# PM12_ATxmega128.net
KiCad netlist of a schematic drawn in Altium Designer
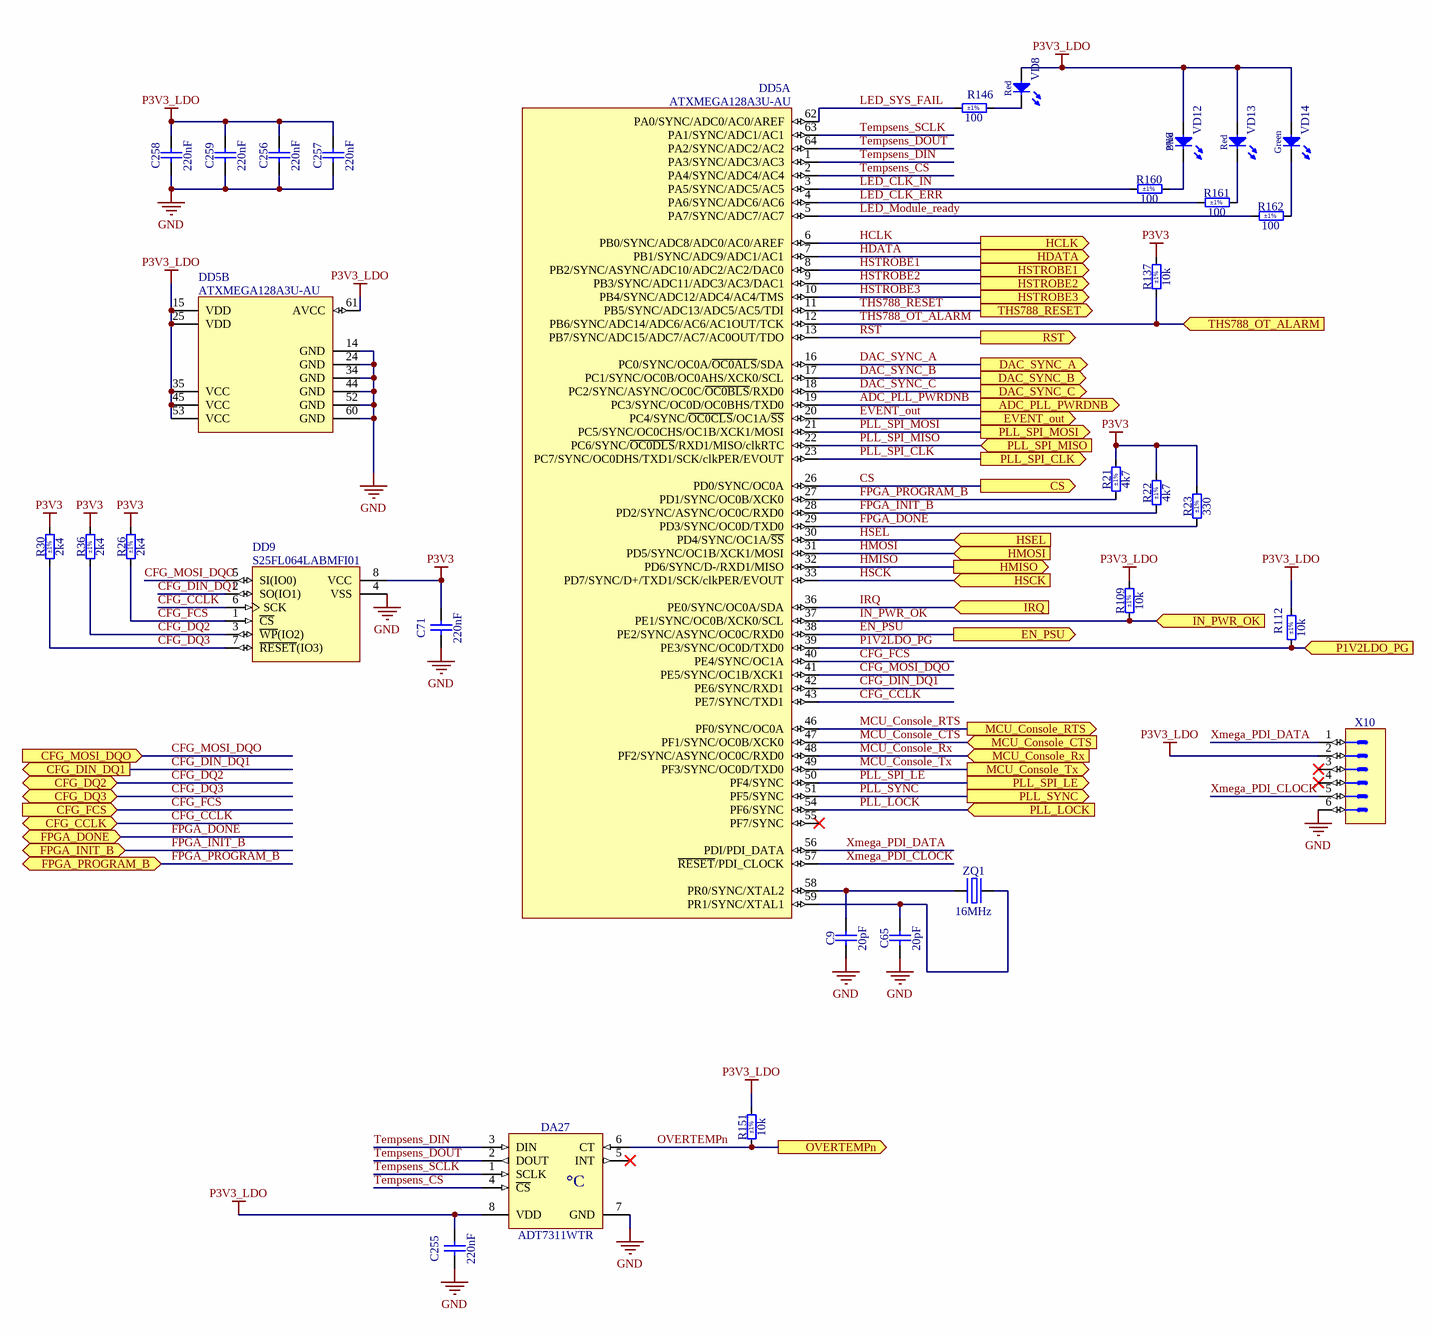
[diagram p0: PM12_ATxmega128.SchDoc]

(export (version "E")
  (design (tool "Eeschema 10.0.6"))
  (components
    (comp (ref "C9")
      (value "20pF")
      (footprint "CAPC2012X135N")
      (description "Non-polarised capacitor")
      (fields
        (field (name "PART NUMBER") "CC0805_20PF_50V_2%_C0G")
        (field (name "VOLTAGE") "50V")
        (field (name "AUTHOR") "CERN DEM HF")
      )
      (libsource (lib "Capacitors") (part "Capacitor - non polarized"))
    )
    (comp (ref "C65")
      (value "20pF")
      (footprint "CAPC2012X135N")
      (description "Non-polarised capacitor")
      (fields
        (field (name "PART NUMBER") "CC0805_20PF_50V_2%_C0G")
        (field (name "VOLTAGE") "50V")
        (field (name "AUTHOR") "CERN DEM HF")
      )
      (libsource (lib "Capacitors") (part "Capacitor - non polarized"))
    )
    (comp (ref "C71")
      (value "220nF")
      (footprint "CAPC2012X135N")
      (description "Non-polarised capacitor")
      (fields
        (field (name "PART NUMBER") "CC0805_220NF_50V_10%_X7R")
        (field (name "VOLTAGE") "50V")
        (field (name "AUTHOR") "CERN DEM JLC")
      )
      (libsource (lib "Capacitors") (part "Capacitor - non polarized"))
    )
    (comp (ref "C255")
      (value "220nF")
      (footprint "CAPC2012X135N")
      (description "Non-polarised capacitor")
      (fields
        (field (name "PART NUMBER") "CC0805_220NF_50V_10%_X7R")
        (field (name "VOLTAGE") "50V")
        (field (name "AUTHOR") "CERN DEM JLC")
      )
      (libsource (lib "Capacitors") (part "Capacitor - non polarized"))
    )
    (comp (ref "C256")
      (value "220nF")
      (footprint "CAPC2012X135N")
      (description "Non-polarised capacitor")
      (fields
        (field (name "PART NUMBER") "CC0805_220NF_50V_10%_X7R")
        (field (name "VOLTAGE") "50V")
        (field (name "AUTHOR") "CERN DEM JLC")
      )
      (libsource (lib "Capacitors") (part "Capacitor - non polarized"))
    )
    (comp (ref "C257")
      (value "220nF")
      (footprint "CAPC2012X135N")
      (description "Non-polarised capacitor")
      (fields
        (field (name "PART NUMBER") "CC0805_220NF_50V_10%_X7R")
        (field (name "VOLTAGE") "50V")
        (field (name "AUTHOR") "CERN DEM JLC")
      )
      (libsource (lib "Capacitors") (part "Capacitor - non polarized"))
    )
    (comp (ref "C258")
      (value "220nF")
      (footprint "CAPC2012X135N")
      (description "Non-polarised capacitor")
      (fields
        (field (name "PART NUMBER") "CC0805_220NF_50V_10%_X7R")
        (field (name "VOLTAGE") "50V")
        (field (name "AUTHOR") "CERN DEM JLC")
      )
      (libsource (lib "Capacitors") (part "Capacitor - non polarized"))
    )
    (comp (ref "C259")
      (value "220nF")
      (footprint "CAPC2012X135N")
      (description "Non-polarised capacitor")
      (fields
        (field (name "PART NUMBER") "CC0805_220NF_50V_10%_X7R")
        (field (name "VOLTAGE") "50V")
        (field (name "AUTHOR") "CERN DEM JLC")
      )
      (libsource (lib "Capacitors") (part "Capacitor - non polarized"))
    )
    (comp (ref "DA27")
      (value "ADT7311WTR")
      (footprint "SOIC127P600X175-8N")
      (description "±0.5°C Accurate, 16-Bit Digital SPI Temperature Sensor")
      (fields (field (name "MANUFACTURER") "ANALOG DEVICES") (field (name "AUTHOR") "CERN DEM HF"))
      (libsource (lib "ICs And Semiconductors") (part "ADT7311WTR"))
    )
    (comp (ref "DD5")
      (value "ATXMEGA128A3U-AU")
      (footprint "QFP80P1600X1600X120-64N")
      (description "8/16-bit XMEGA A3BU 32MHz Microcontroller With 256KBytes of in-System Self-Programmable Flash")
      (fields (field (name "MANUFACTURER") "MICROCHIP TECHNOLOGY") (field (name "AUTHOR") "CERN DEM HF"))
      (libsource (lib "ICs And Semiconductors") (part "ATXMEGA128A3U-AU"))
    )
    (comp (ref "DD9")
      (value "S25FL064LABMFI01")
      (footprint "SOIC127P800X216-8N")
      (description "64 Mb (8 MB), 3V, FL-L SPI Flash Memory")
      (fields (field (name "MANUFACTURER") "INFINEON") (field (name "AUTHOR") "CERN DEM HF"))
      (libsource (lib "ICs And Semiconductors") (part "S25FL064LABMFI01"))
    )
    (comp (ref "R21")
      (value "4k7")
      (footprint "RESC2012X60N")
      (description "Resistor - 1%")
      (fields
        (field (name "TOLERANCE") "±1%")
        (field (name "PART NUMBER") "R0805_4K7_1%_0.125W_100PPM")
        (field (name "POWER") "0.125W")
        (field (name "AUTHOR") "CERN DEM JLC")
      )
      (libsource (lib "Resistors") (part "Resistor - 1%"))
    )
    (comp (ref "R22")
      (value "4k7")
      (footprint "RESC2012X60N")
      (description "Resistor - 1%")
      (fields
        (field (name "TOLERANCE") "±1%")
        (field (name "PART NUMBER") "R0805_4K7_1%_0.125W_100PPM")
        (field (name "POWER") "0.125W")
        (field (name "AUTHOR") "CERN DEM JLC")
      )
      (libsource (lib "Resistors") (part "Resistor - 1%"))
    )
    (comp (ref "R23")
      (value "330")
      (footprint "RESC2012X60N")
      (description "Resistor - 1%")
      (fields
        (field (name "TOLERANCE") "±1%")
        (field (name "PART NUMBER") "R0805_330R_1%_0.125W_100PPM")
        (field (name "POWER") "0.125W")
        (field (name "AUTHOR") "CERN DEM JLC")
      )
      (libsource (lib "Resistors") (part "Resistor - 1%"))
    )
    (comp (ref "R26")
      (value "2k4")
      (footprint "RESC2012X60N")
      (description "Resistor - 1%")
      (fields
        (field (name "TOLERANCE") "±1%")
        (field (name "PART NUMBER") "R0805_2K4_1%_0.125W_100PPM")
        (field (name "POWER") "0.125W")
        (field (name "AUTHOR") "CERN DEM JLC")
      )
      (libsource (lib "Resistors") (part "Resistor - 1%"))
    )
    (comp (ref "R30")
      (value "2k4")
      (footprint "RESC2012X60N")
      (description "Resistor - 1%")
      (fields
        (field (name "TOLERANCE") "±1%")
        (field (name "PART NUMBER") "R0805_2K4_1%_0.125W_100PPM")
        (field (name "POWER") "0.125W")
        (field (name "AUTHOR") "CERN DEM JLC")
      )
      (libsource (lib "Resistors") (part "Resistor - 1%"))
    )
    (comp (ref "R36")
      (value "2k4")
      (footprint "RESC2012X60N")
      (description "Resistor - 1%")
      (fields
        (field (name "TOLERANCE") "±1%")
        (field (name "PART NUMBER") "R0805_2K4_1%_0.125W_100PPM")
        (field (name "POWER") "0.125W")
        (field (name "AUTHOR") "CERN DEM JLC")
      )
      (libsource (lib "Resistors") (part "Resistor - 1%"))
    )
    (comp (ref "R109")
      (value "10k")
      (footprint "RESC2012X60N")
      (description "Resistor - 1%")
      (fields
        (field (name "TOLERANCE") "±1%")
        (field (name "PART NUMBER") "R0805_10K_1%_0.125W_100PPM")
        (field (name "POWER") "0.125W")
        (field (name "AUTHOR") "CERN DEM JLC")
      )
      (libsource (lib "Resistors") (part "Resistor - 1%"))
    )
    (comp (ref "R112")
      (value "10k")
      (footprint "RESC2012X60N")
      (description "Resistor - 1%")
      (fields
        (field (name "TOLERANCE") "±1%")
        (field (name "PART NUMBER") "R0805_10K_1%_0.125W_100PPM")
        (field (name "POWER") "0.125W")
        (field (name "AUTHOR") "CERN DEM JLC")
      )
      (libsource (lib "Resistors") (part "Resistor - 1%"))
    )
    (comp (ref "R137")
      (value "10k")
      (footprint "RESC2012X60N")
      (description "Resistor - 1%")
      (fields
        (field (name "TOLERANCE") "±1%")
        (field (name "PART NUMBER") "R0805_10K_1%_0.125W_100PPM")
        (field (name "POWER") "0.125W")
        (field (name "AUTHOR") "CERN DEM JLC")
      )
      (libsource (lib "Resistors") (part "Resistor - 1%"))
    )
    (comp (ref "R146")
      (value "100")
      (footprint "RESC2012X60N")
      (description "Resistor - 1%")
      (fields
        (field (name "TOLERANCE") "±1%")
        (field (name "PART NUMBER") "R0805_100R_1%_0.125W_100PPM")
        (field (name "POWER") "0.125W")
        (field (name "AUTHOR") "CERN DEM JLC")
      )
      (libsource (lib "Resistors") (part "Resistor - 1%"))
    )
    (comp (ref "R151")
      (value "10k")
      (footprint "RESC2012X60N")
      (description "Resistor - 1%")
      (fields
        (field (name "TOLERANCE") "±1%")
        (field (name "PART NUMBER") "R0805_10K_1%_0.125W_100PPM")
        (field (name "POWER") "0.125W")
        (field (name "AUTHOR") "CERN DEM JLC")
      )
      (libsource (lib "Resistors") (part "Resistor - 1%"))
    )
    (comp (ref "R160")
      (value "100")
      (footprint "RESC2012X60N")
      (description "Resistor - 1%")
      (fields
        (field (name "TOLERANCE") "±1%")
        (field (name "PART NUMBER") "R0805_100R_1%_0.125W_100PPM")
        (field (name "POWER") "0.125W")
        (field (name "AUTHOR") "CERN DEM JLC")
      )
      (libsource (lib "Resistors") (part "Resistor - 1%"))
    )
    (comp (ref "R161")
      (value "100")
      (footprint "RESC2012X60N")
      (description "Resistor - 1%")
      (fields
        (field (name "TOLERANCE") "±1%")
        (field (name "PART NUMBER") "R0805_100R_1%_0.125W_100PPM")
        (field (name "POWER") "0.125W")
        (field (name "AUTHOR") "CERN DEM JLC")
      )
      (libsource (lib "Resistors") (part "Resistor - 1%"))
    )
    (comp (ref "R162")
      (value "100")
      (footprint "RESC2012X60N")
      (description "Resistor - 1%")
      (fields
        (field (name "TOLERANCE") "±1%")
        (field (name "PART NUMBER") "R0805_100R_1%_0.125W_100PPM")
        (field (name "POWER") "0.125W")
        (field (name "AUTHOR") "CERN DEM JLC")
      )
      (libsource (lib "Resistors") (part "Resistor - 1%"))
    )
    (comp (ref "VD8")
      (value "Red")
      (footprint "LED_KINGBRIGHT_KPT-2012SURCK")
      (description "LED Red 1C 2A")
      (fields
        (field (name "PART NUMBER") "LED_KINGBRIGHT_KPT-2012SURCK")
        (field (name "MANUFACTURER") "KINGBRIGHT")
        (field (name "AUTHOR") "CERN DEM BC")
      )
      (libsource (lib "ICs And Semiconductors") (part "LED Red 1C 2A"))
    )
    (comp (ref "VD12")
      (value "Blue")
      (footprint "LED_KINGBRIGHT_KPT-2012VBC-D")
      (description "LED Blue 1C 2A")
      (fields
        (field (name "PART NUMBER") "LED_KINGBRIGHT_KPT-2012VBC-D")
        (field (name "MANUFACTURER") "KINGBRIGHT")
        (field (name "AUTHOR") "CERN DEM BC")
      )
      (libsource (lib "ICs And Semiconductors") (part "LED Blue 1C 2A"))
    )
    (comp (ref "VD13")
      (value "Red")
      (footprint "LED_KINGBRIGHT_KPT-2012SURCK")
      (description "LED Red 1C 2A")
      (fields
        (field (name "PART NUMBER") "LED_KINGBRIGHT_KPT-2012SURCK")
        (field (name "MANUFACTURER") "KINGBRIGHT")
        (field (name "AUTHOR") "CERN DEM BC")
      )
      (libsource (lib "ICs And Semiconductors") (part "LED Red 1C 2A"))
    )
    (comp (ref "VD14")
      (value "Green")
      (footprint "LED_KINGBRIGHT_KP-2012LSGC")
      (description "LED Green 1C 2A")
      (fields
        (field (name "PART NUMBER") "LED_KINGBRIGHT_KP-2012LSGC")
        (field (name "MANUFACTURER") "KINGBRIGHT")
        (field (name "AUTHOR") "CERN DEM BC")
      )
      (libsource (lib "ICs And Semiconductors") (part "LED Green 1C 2A"))
    )
    (comp (ref "X10")
      (value "~")
      (footprint "CONNFLY_DS1013-06SSIB1-B-0")
      (description "Connector 6 Male")
      (fields
        (field (name "PART NUMBER") "CONNFLY_DS1013-06SSIB1-B-0")
        (field (name "MANUFACTURER") "CONNFLY")
        (field (name "AUTHOR") "CERN DEM HF")
      )
      (libsource (lib "Connectors") (part "Connector 6 Male"))
    )
    (comp (ref "ZQ1")
      (value "16MHz")
      (footprint "XTAL_ABRACON_ABL")
      (description "Quartz Crystal")
      (fields
        (field (name "PART NUMBER") "XTAL_16MHZ_ABRACON_ABL-16.000MHZ-B1U")
        (field (name "MANUFACTURER") "ABRACON")
        (field (name "AUTHOR") "CERN DEM HF")
      )
      (libsource (lib "ICs And Semiconductors") (part "Quartz Crystal"))
    )
  )
  (nets
    (net (code "1") (name "/ADC_PLL_PWRDNB") (class "Default")
      (node (ref "DD5") (pin "19") (pinfunction "PC3/SYNC/OC0D/OC0BHS/TXD0_19") (pintype "bidirectional"))
    )
    (net (code "2") (name "/CFG_CCLK") (class "Default")
      (node (ref "DD5") (pin "43") (pinfunction "PE7/SYNC/TXD1_43") (pintype "bidirectional"))
      (node (ref "DD9") (pin "6") (pinfunction "SCK_6") (pintype "input"))
    )
    (net (code "3") (name "/CFG_DIN_DQ1") (class "Default")
      (node (ref "DD5") (pin "42") (pinfunction "PE6/SYNC/RXD1_42") (pintype "bidirectional"))
      (node (ref "DD9") (pin "2") (pinfunction "SO(IO1)_2") (pintype "bidirectional"))
    )
    (net (code "4") (name "/CFG_DQ2") (class "Default")
      (node (ref "DD9") (pin "3") (pinfunction "~{WP}(IO2)_3") (pintype "bidirectional"))
      (node (ref "R36") (pin "1") (pinfunction "1_1") (pintype "passive"))
    )
    (net (code "5") (name "/CFG_DQ3") (class "Default")
      (node (ref "DD9") (pin "7") (pinfunction "~{RESET}(IO3)_7") (pintype "bidirectional"))
      (node (ref "R30") (pin "1") (pinfunction "1_1") (pintype "passive"))
    )
    (net (code "6") (name "/CFG_FCS") (class "Default")
      (node (ref "DD5") (pin "40") (pinfunction "PE4/SYNC/OC1A_40") (pintype "bidirectional"))
      (node (ref "DD9") (pin "1") (pinfunction "~{CS}_1") (pintype "input"))
      (node (ref "R26") (pin "1") (pinfunction "1_1") (pintype "passive"))
    )
    (net (code "7") (name "/CFG_MOSI_DQO") (class "Default")
      (node (ref "DD5") (pin "41") (pinfunction "PE5/SYNC/OC1B/XCK1_41") (pintype "bidirectional"))
      (node (ref "DD9") (pin "5") (pinfunction "SI(IO0)_5") (pintype "bidirectional"))
    )
    (net (code "8") (name "/CS") (class "Default")
      (node (ref "DD5") (pin "26") (pinfunction "PD0/SYNC/OC0A_26") (pintype "bidirectional"))
    )
    (net (code "9") (name "/DAC_SYNC_A") (class "Default")
      (node (ref "DD5") (pin "16") (pinfunction "PC0/SYNC/OC0A/~{OC0ALS}/SDA_16") (pintype "bidirectional"))
    )
    (net (code "10") (name "/DAC_SYNC_B") (class "Default")
      (node (ref "DD5") (pin "17") (pinfunction "PC1/SYNC/OC0B/OC0AHS/XCK0/SCL_17") (pintype "bidirectional"))
    )
    (net (code "11") (name "/DAC_SYNC_C") (class "Default")
      (node (ref "DD5") (pin "18") (pinfunction "PC2/SYNC/ASYNC/OC0C/~{OC0BLS}/RXD0_18") (pintype "bidirectional"))
    )
    (net (code "12") (name "/EN_PSU") (class "Default")
      (node (ref "DD5") (pin "38") (pinfunction "PE2/SYNC/ASYNC/OC0C/RXD0_38") (pintype "bidirectional"))
    )
    (net (code "13") (name "/EVENT_out") (class "Default")
      (node (ref "DD5") (pin "20") (pinfunction "PC4/SYNC/~{OC0CLS}/OC1A/~{SS}_20") (pintype "bidirectional"))
    )
    (net (code "14") (name "/FPGA_DONE") (class "Default")
      (node (ref "DD5") (pin "29") (pinfunction "PD3/SYNC/OC0D/TXD0_29") (pintype "bidirectional"))
      (node (ref "R23") (pin "1") (pinfunction "1_1") (pintype "passive"))
    )
    (net (code "15") (name "/FPGA_INIT_B") (class "Default")
      (node (ref "DD5") (pin "28") (pinfunction "PD2/SYNC/ASYNC/OC0C/RXD0_28") (pintype "bidirectional"))
      (node (ref "R22") (pin "1") (pinfunction "1_1") (pintype "passive"))
    )
    (net (code "16") (name "/FPGA_PROGRAM_B") (class "Default")
      (node (ref "DD5") (pin "27") (pinfunction "PD1/SYNC/OC0B/XCK0_27") (pintype "bidirectional"))
      (node (ref "R21") (pin "1") (pinfunction "1_1") (pintype "passive"))
    )
    (net (code "17") (name "/HCLK") (class "Default")
      (node (ref "DD5") (pin "6") (pinfunction "PB0/SYNC/ADC8/ADC0/AC0/AREF_6") (pintype "bidirectional"))
    )
    (net (code "18") (name "/HDATA") (class "Default")
      (node (ref "DD5") (pin "7") (pinfunction "PB1/SYNC/ADC9/ADC1/AC1_7") (pintype "bidirectional"))
    )
    (net (code "19") (name "/HMISO") (class "Default")
      (node (ref "DD5") (pin "32") (pinfunction "PD6/SYNC/D-/RXD1/MISO_32") (pintype "bidirectional"))
    )
    (net (code "20") (name "/HMOSI") (class "Default")
      (node (ref "DD5") (pin "31") (pinfunction "PD5/SYNC/OC1B/XCK1/MOSI_31") (pintype "bidirectional"))
    )
    (net (code "21") (name "/HSCK") (class "Default")
      (node (ref "DD5") (pin "33") (pinfunction "PD7/SYNC/D+/TXD1/SCK/clkPER/EVOUT_33") (pintype "bidirectional"))
    )
    (net (code "22") (name "/HSEL") (class "Default")
      (node (ref "DD5") (pin "30") (pinfunction "PD4/SYNC/OC1A/~{SS}_30") (pintype "bidirectional"))
    )
    (net (code "23") (name "/HSTROBE1") (class "Default")
      (node (ref "DD5") (pin "8") (pinfunction "PB2/SYNC/ASYNC/ADC10/ADC2/AC2/DAC0_8") (pintype "bidirectional"))
    )
    (net (code "24") (name "/HSTROBE2") (class "Default")
      (node (ref "DD5") (pin "9") (pinfunction "PB3/SYNC/ADC11/ADC3/AC3/DAC1_9") (pintype "bidirectional"))
    )
    (net (code "25") (name "/HSTROBE3") (class "Default")
      (node (ref "DD5") (pin "10") (pinfunction "PB4/SYNC/ADC12/ADC4/AC4/TMS_10") (pintype "bidirectional"))
    )
    (net (code "26") (name "/IN_PWR_OK") (class "Default")
      (node (ref "DD5") (pin "37") (pinfunction "PE1/SYNC/OC0B/XCK0/SCL_37") (pintype "bidirectional"))
      (node (ref "R109") (pin "1") (pinfunction "1_1") (pintype "passive"))
    )
    (net (code "27") (name "/IRQ") (class "Default")
      (node (ref "DD5") (pin "36") (pinfunction "PE0/SYNC/OC0A/SDA_36") (pintype "bidirectional"))
    )
    (net (code "28") (name "/LED_CLK_ERR") (class "Default")
      (node (ref "DD5") (pin "4") (pinfunction "PA6/SYNC/ADC6/AC6_4") (pintype "bidirectional"))
      (node (ref "R161") (pin "1") (pinfunction "1_1") (pintype "passive"))
    )
    (net (code "29") (name "/LED_CLK_IN") (class "Default")
      (node (ref "DD5") (pin "3") (pinfunction "PA5/SYNC/ADC5/AC5_3") (pintype "bidirectional"))
      (node (ref "R160") (pin "1") (pinfunction "1_1") (pintype "passive"))
    )
    (net (code "30") (name "/LED_Module_ready") (class "Default")
      (node (ref "DD5") (pin "5") (pinfunction "PA7/SYNC/ADC7/AC7_5") (pintype "bidirectional"))
      (node (ref "R162") (pin "1") (pinfunction "1_1") (pintype "passive"))
    )
    (net (code "31") (name "/LED_SYS_FAIL") (class "Default")
      (node (ref "DD5") (pin "62") (pinfunction "PA0/SYNC/ADC0/AC0/AREF_62") (pintype "bidirectional"))
      (node (ref "R146") (pin "1") (pinfunction "1_1") (pintype "passive"))
    )
    (net (code "32") (name "/MCU_Console_CTS") (class "Default")
      (node (ref "DD5") (pin "47") (pinfunction "PF1/SYNC/OC0B/XCK0_47") (pintype "bidirectional"))
    )
    (net (code "33") (name "/MCU_Console_RTS") (class "Default")
      (node (ref "DD5") (pin "46") (pinfunction "PF0/SYNC/OC0A_46") (pintype "bidirectional"))
    )
    (net (code "34") (name "/MCU_Console_Rx") (class "Default")
      (node (ref "DD5") (pin "48") (pinfunction "PF2/SYNC/ASYNC/OC0C/RXD0_48") (pintype "bidirectional"))
    )
    (net (code "35") (name "/MCU_Console_Tx") (class "Default")
      (node (ref "DD5") (pin "49") (pinfunction "PF3/SYNC/OC0D/TXD0_49") (pintype "bidirectional"))
    )
    (net (code "36") (name "/OVERTEMPn") (class "Default")
      (node (ref "DA27") (pin "6") (pinfunction "CT_6") (pintype "input"))
      (node (ref "R151") (pin "1") (pinfunction "1_1") (pintype "passive"))
    )
    (net (code "37") (name "/P1V2LDO_PG") (class "Default")
      (node (ref "DD5") (pin "39") (pinfunction "PE3/SYNC/OC0D/TXD0_39") (pintype "bidirectional"))
      (node (ref "R112") (pin "1") (pinfunction "1_1") (pintype "passive"))
    )
    (net (code "38") (name "/PLL_LOCK") (class "Default")
      (node (ref "DD5") (pin "54") (pinfunction "PF6/SYNC_54") (pintype "bidirectional"))
    )
    (net (code "39") (name "/PLL_SPI_CLK") (class "Default")
      (node (ref "DD5") (pin "23") (pinfunction "PC7/SYNC/OC0DHS/TXD1/SCK/clkPER/EVOUT_23") (pintype "bidirectional"))
    )
    (net (code "40") (name "/PLL_SPI_LE") (class "Default")
      (node (ref "DD5") (pin "50") (pinfunction "PF4/SYNC_50") (pintype "bidirectional"))
    )
    (net (code "41") (name "/PLL_SPI_MISO") (class "Default")
      (node (ref "DD5") (pin "22") (pinfunction "PC6/SYNC/~{OC0DLS}/RXD1/MISO/clkRTC_22") (pintype "bidirectional"))
    )
    (net (code "42") (name "/PLL_SPI_MOSI") (class "Default")
      (node (ref "DD5") (pin "21") (pinfunction "PC5/SYNC/OC0CHS/OC1B/XCK1/MOSI_21") (pintype "bidirectional"))
    )
    (net (code "43") (name "/PLL_SYNC") (class "Default")
      (node (ref "DD5") (pin "51") (pinfunction "PF5/SYNC_51") (pintype "bidirectional"))
    )
    (net (code "44") (name "/RST") (class "Default")
      (node (ref "DD5") (pin "13") (pinfunction "PB7/SYNC/ADC15/ADC7/AC7/AC0OUT/TDO_13") (pintype "bidirectional"))
    )
    (net (code "45") (name "/THS788_OT_ALARM") (class "Default")
      (node (ref "DD5") (pin "12") (pinfunction "PB6/SYNC/ADC14/ADC6/AC6/AC1OUT/TCK_12") (pintype "bidirectional"))
      (node (ref "R137") (pin "1") (pinfunction "1_1") (pintype "passive"))
    )
    (net (code "46") (name "/THS788_RESET") (class "Default")
      (node (ref "DD5") (pin "11") (pinfunction "PB5/SYNC/ADC13/ADC5/AC5/TDI_11") (pintype "bidirectional"))
    )
    (net (code "47") (name "/Tempsens_CS") (class "Default")
      (node (ref "DA27") (pin "4") (pinfunction "~{CS}_4") (pintype "input"))
      (node (ref "DD5") (pin "2") (pinfunction "PA4/SYNC/ADC4/AC4_2") (pintype "bidirectional"))
    )
    (net (code "48") (name "/Tempsens_DIN") (class "Default")
      (node (ref "DA27") (pin "3") (pinfunction "DIN_3") (pintype "input"))
      (node (ref "DD5") (pin "1") (pinfunction "PA3/SYNC/ADC3/AC3_1") (pintype "bidirectional"))
    )
    (net (code "49") (name "/Tempsens_DOUT") (class "Default")
      (node (ref "DA27") (pin "2") (pinfunction "DOUT_2") (pintype "output"))
      (node (ref "DD5") (pin "64") (pinfunction "PA2/SYNC/ADC2/AC2_64") (pintype "bidirectional"))
    )
    (net (code "50") (name "/Tempsens_SCLK") (class "Default")
      (node (ref "DA27") (pin "1") (pinfunction "SCLK_1") (pintype "input"))
      (node (ref "DD5") (pin "63") (pinfunction "PA1/SYNC/ADC1/AC1_63") (pintype "bidirectional"))
    )
    (net (code "51") (name "/Xmega_PDI_CLOCK") (class "Default")
      (node (ref "DD5") (pin "57") (pinfunction "~{RESET}/PDI_CLOCK_57") (pintype "bidirectional"))
      (node (ref "X10") (pin "5") (pinfunction "5_5") (pintype "bidirectional"))
    )
    (net (code "52") (name "/Xmega_PDI_DATA") (class "Default")
      (node (ref "DD5") (pin "56") (pinfunction "PDI/PDI_DATA_56") (pintype "bidirectional"))
      (node (ref "X10") (pin "1") (pinfunction "1_1") (pintype "bidirectional"))
    )
    (net (code "53") (name "GND") (class "Default")
      (node (ref "C255") (pin "1") (pinfunction "1_1") (pintype "passive"))
      (node (ref "C256") (pin "1") (pinfunction "1_1") (pintype "passive"))
      (node (ref "C257") (pin "1") (pinfunction "1_1") (pintype "passive"))
      (node (ref "C258") (pin "1") (pinfunction "1_1") (pintype "passive"))
      (node (ref "C259") (pin "1") (pinfunction "1_1") (pintype "passive"))
      (node (ref "C65") (pin "1") (pinfunction "1_1") (pintype "passive"))
      (node (ref "C71") (pin "1") (pinfunction "1_1") (pintype "passive"))
      (node (ref "C9") (pin "1") (pinfunction "1_1") (pintype "passive"))
      (node (ref "DA27") (pin "7") (pinfunction "GND_7") (pintype "power_in"))
      (node (ref "DD5") (pin "14") (pinfunction "GND_14") (pintype "power_in"))
      (node (ref "DD5") (pin "24") (pinfunction "GND_24") (pintype "power_in"))
      (node (ref "DD5") (pin "34") (pinfunction "GND_34") (pintype "power_in"))
      (node (ref "DD5") (pin "44") (pinfunction "GND_44") (pintype "power_in"))
      (node (ref "DD5") (pin "52") (pinfunction "GND_52") (pintype "power_in"))
      (node (ref "DD5") (pin "60") (pinfunction "GND_60") (pintype "power_in"))
      (node (ref "DD9") (pin "4") (pinfunction "VSS_4") (pintype "power_in"))
      (node (ref "X10") (pin "6") (pinfunction "6_6") (pintype "bidirectional"))
    )
    (net (code "54") (name "Net-(DD5A-PR0{slash}SYNC{slash}XTAL2)") (class "Default")
      (node (ref "C9") (pin "2") (pinfunction "2_2") (pintype "passive"))
      (node (ref "DD5") (pin "58") (pinfunction "PR0/SYNC/XTAL2_58") (pintype "bidirectional"))
      (node (ref "ZQ1") (pin "1") (pinfunction "OSC1_1") (pintype "passive"))
    )
    (net (code "55") (name "Net-(DD5A-PR1{slash}SYNC{slash}XTAL1)") (class "Default")
      (node (ref "C65") (pin "2") (pinfunction "2_2") (pintype "passive"))
      (node (ref "DD5") (pin "59") (pinfunction "PR1/SYNC/XTAL1_59") (pintype "bidirectional"))
      (node (ref "ZQ1") (pin "2") (pinfunction "OSC2_2") (pintype "passive"))
    )
    (net (code "56") (name "Net-(VD8-C)") (class "Default")
      (node (ref "R146") (pin "2") (pinfunction "2_2") (pintype "passive"))
      (node (ref "VD8") (pin "1") (pinfunction "C_1") (pintype "passive"))
    )
    (net (code "57") (name "Net-(VD12-C)") (class "Default")
      (node (ref "R160") (pin "2") (pinfunction "2_2") (pintype "passive"))
      (node (ref "VD12") (pin "1") (pinfunction "C_1") (pintype "passive"))
    )
    (net (code "58") (name "Net-(VD13-C)") (class "Default")
      (node (ref "R161") (pin "2") (pinfunction "2_2") (pintype "passive"))
      (node (ref "VD13") (pin "1") (pinfunction "C_1") (pintype "passive"))
    )
    (net (code "59") (name "Net-(VD14-C)") (class "Default")
      (node (ref "R162") (pin "2") (pinfunction "2_2") (pintype "passive"))
      (node (ref "VD14") (pin "1") (pinfunction "C_1") (pintype "passive"))
    )
    (net (code "60") (name "P3V3") (class "Default")
      (node (ref "C71") (pin "2") (pinfunction "2_2") (pintype "passive"))
      (node (ref "DD9") (pin "8") (pinfunction "VCC_8") (pintype "power_in"))
      (node (ref "R137") (pin "2") (pinfunction "2_2") (pintype "passive"))
      (node (ref "R21") (pin "2") (pinfunction "2_2") (pintype "passive"))
      (node (ref "R22") (pin "2") (pinfunction "2_2") (pintype "passive"))
      (node (ref "R23") (pin "2") (pinfunction "2_2") (pintype "passive"))
      (node (ref "R26") (pin "2") (pinfunction "2_2") (pintype "passive"))
      (node (ref "R30") (pin "2") (pinfunction "2_2") (pintype "passive"))
      (node (ref "R36") (pin "2") (pinfunction "2_2") (pintype "passive"))
    )
    (net (code "61") (name "P3V3_LDO") (class "Default")
      (node (ref "C255") (pin "2") (pinfunction "2_2") (pintype "passive"))
      (node (ref "C256") (pin "2") (pinfunction "2_2") (pintype "passive"))
      (node (ref "C257") (pin "2") (pinfunction "2_2") (pintype "passive"))
      (node (ref "C258") (pin "2") (pinfunction "2_2") (pintype "passive"))
      (node (ref "C259") (pin "2") (pinfunction "2_2") (pintype "passive"))
      (node (ref "DA27") (pin "8") (pinfunction "VDD_8") (pintype "power_in"))
      (node (ref "DD5") (pin "15") (pinfunction "VDD_15") (pintype "power_in"))
      (node (ref "DD5") (pin "25") (pinfunction "VDD_25") (pintype "power_in"))
      (node (ref "DD5") (pin "35") (pinfunction "VCC_35") (pintype "power_in"))
      (node (ref "DD5") (pin "45") (pinfunction "VCC_45") (pintype "power_in"))
      (node (ref "DD5") (pin "53") (pinfunction "VCC_53") (pintype "power_in"))
      (node (ref "DD5") (pin "61") (pinfunction "AVCC_61") (pintype "bidirectional"))
      (node (ref "R109") (pin "2") (pinfunction "2_2") (pintype "passive"))
      (node (ref "R112") (pin "2") (pinfunction "2_2") (pintype "passive"))
      (node (ref "R151") (pin "2") (pinfunction "2_2") (pintype "passive"))
      (node (ref "VD12") (pin "2") (pinfunction "A_2") (pintype "passive"))
      (node (ref "VD13") (pin "2") (pinfunction "A_2") (pintype "passive"))
      (node (ref "VD14") (pin "2") (pinfunction "A_2") (pintype "passive"))
      (node (ref "VD8") (pin "2") (pinfunction "A_2") (pintype "passive"))
      (node (ref "X10") (pin "2") (pinfunction "2_2") (pintype "bidirectional"))
    )
    (net (code "62") (name "unconnected-(DA27-INT-Pad5)") (class "Default")
      (node (ref "DA27") (pin "5") (pinfunction "INT_5") (pintype "output+no_connect"))
    )
    (net (code "63") (name "unconnected-(DD5A-PF7{slash}SYNC-Pad55)") (class "Default")
      (node (ref "DD5") (pin "55") (pinfunction "PF7/SYNC_55") (pintype "bidirectional+no_connect"))
    )
    (net (code "64") (name "unconnected-(X10-Pad3)") (class "Default")
      (node (ref "X10") (pin "3") (pinfunction "3_3") (pintype "bidirectional+no_connect"))
    )
    (net (code "65") (name "unconnected-(X10-Pad4)") (class "Default")
      (node (ref "X10") (pin "4") (pinfunction "4_4") (pintype "bidirectional+no_connect"))
    )
  )
)
